# Sheet2.net
KiCad netlist of a schematic drawn in Altium Designer
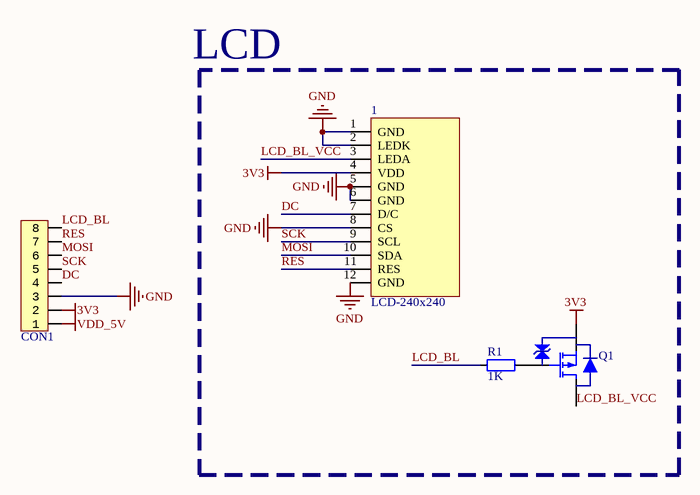
[diagram p0: Sheet2.SchDoc]

(export (version "E")
  (design (tool "Eeschema 10.0.6"))
  (components
    (comp (ref "1")
      (value "LCD-240x240")
      (footprint "LCD-240x240-NoHole")
      (description "显示屏")
      (libsource (lib "mLib") (part "LCD-240x240"))
    )
    (comp (ref "CON1")
      (value "FFC_0.5_8")
      (footprint "FFC_0.5_8")
      (description "FFC")
      (libsource (lib "KitSprout") (part "FFC_0.5_8"))
    )
    (comp (ref "Q1")
      (value "AO3415A")
      (footprint "SOT23-3")
      (description "MOSFET")
      (fields (field (name "PUBLISHER") "Altium Limited"))
      (libsource (lib "MyPcbLib") (part "AO3415A"))
    )
    (comp (ref "R1")
      (value "1K")
      (footprint "RES_0402")
      (description "Resistor")
      (libsource (lib "MyPcbLib") (part "电阻-0402"))
    )
  )
  (nets
    (net (code "1") (name "/DC") (class "Default")
      (node (ref "1") (pin "7") (pinfunction "D/C_7") (pintype "passive"))
      (node (ref "CON1") (pin "4") (pinfunction "4_4") (pintype "passive"))
    )
    (net (code "2") (name "/LCD_BL") (class "Default")
      (node (ref "CON1") (pin "8") (pinfunction "8_8") (pintype "passive"))
      (node (ref "R1") (pin "1") (pinfunction "1_1") (pintype "passive"))
    )
    (net (code "3") (name "/LCD_BL_VCC") (class "Default")
      (node (ref "1") (pin "3") (pinfunction "LEDA_3") (pintype "passive"))
      (node (ref "Q1") (pin "3") (pinfunction "D_3") (pintype "passive"))
    )
    (net (code "4") (name "/MOSI") (class "Default")
      (node (ref "1") (pin "10") (pinfunction "SDA_10") (pintype "passive"))
      (node (ref "CON1") (pin "6") (pinfunction "6_6") (pintype "passive"))
    )
    (net (code "5") (name "/RES") (class "Default")
      (node (ref "1") (pin "11") (pinfunction "RES_11") (pintype "passive"))
      (node (ref "CON1") (pin "7") (pinfunction "7_7") (pintype "passive"))
    )
    (net (code "6") (name "/SCK") (class "Default")
      (node (ref "1") (pin "9") (pinfunction "SCL_9") (pintype "passive"))
      (node (ref "CON1") (pin "5") (pinfunction "5_5") (pintype "passive"))
    )
    (net (code "7") (name "3V3") (class "Default")
      (node (ref "1") (pin "4") (pinfunction "VDD_4") (pintype "passive"))
      (node (ref "CON1") (pin "2") (pinfunction "2_2") (pintype "passive"))
      (node (ref "Q1") (pin "2") (pinfunction "S_2") (pintype "passive"))
    )
    (net (code "8") (name "GND") (class "Default")
      (node (ref "1") (pin "1") (pinfunction "GND_1") (pintype "passive"))
      (node (ref "1") (pin "12") (pinfunction "GND_12") (pintype "passive"))
      (node (ref "1") (pin "2") (pinfunction "LEDK_2") (pintype "passive"))
      (node (ref "1") (pin "5") (pinfunction "GND_5") (pintype "passive"))
      (node (ref "1") (pin "6") (pinfunction "GND_6") (pintype "passive"))
      (node (ref "1") (pin "8") (pinfunction "CS_8") (pintype "passive"))
      (node (ref "CON1") (pin "3") (pinfunction "3_3") (pintype "passive"))
    )
    (net (code "9") (name "Net-(Q1-G)") (class "Default")
      (node (ref "Q1") (pin "1") (pinfunction "G_1") (pintype "passive"))
      (node (ref "R1") (pin "2") (pinfunction "2_2") (pintype "passive"))
    )
    (net (code "10") (name "VDD_5V") (class "Default")
      (node (ref "CON1") (pin "1") (pinfunction "1_1") (pintype "passive"))
    )
  )
)
